# LEDDriver_v_6.net
KiCad netlist of a schematic drawn in EAGLE
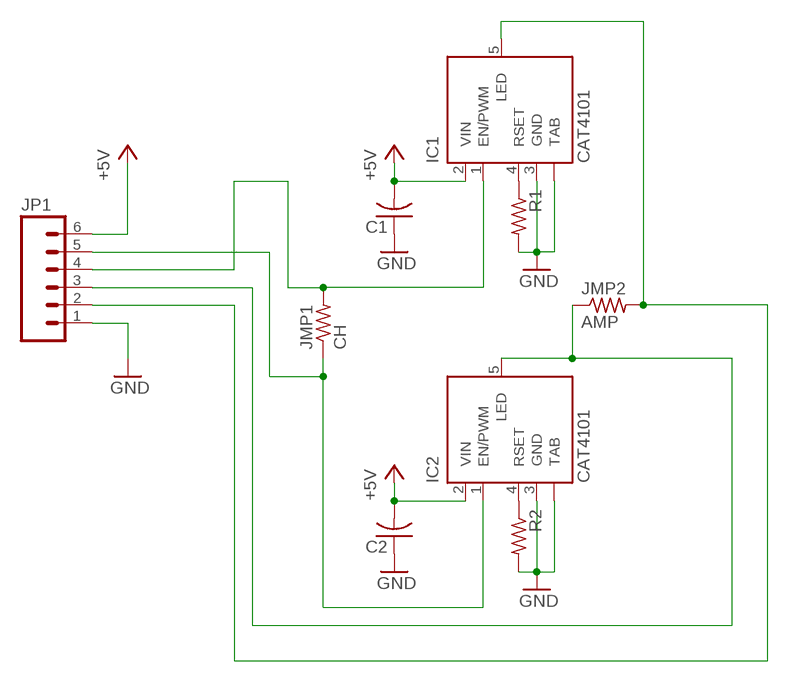
[diagram p0: schematic, sheet 1]

(export (version "E")
  (design (tool "Eeschema 10.0.6"))
  (components
    (comp (ref "C1")
      (value "C-USC1206")
      (footprint "eagle-import:C1206")
      (libsource (lib "eagle-import") (part "C-USC1206"))
    )
    (comp (ref "C2")
      (value "C-USC1206")
      (footprint "eagle-import:C1206")
      (libsource (lib "eagle-import") (part "C-USC1206"))
    )
    (comp (ref "IC1")
      (value "CAT4101")
      (footprint "eagle-import:TO263_5")
      (fields (field (name "MPN") "CAT4101TV-T75"))
      (libsource (lib "eagle-import") (part "CAT4101"))
    )
    (comp (ref "IC2")
      (value "CAT4101")
      (footprint "eagle-import:TO263_5")
      (fields (field (name "MPN") "CAT4101TV-T75"))
      (libsource (lib "eagle-import") (part "CAT4101"))
    )
    (comp (ref "JMP1")
      (value "CH")
      (footprint "eagle-import:R1206")
      (libsource (lib "eagle-import") (part "R-US_R1206"))
    )
    (comp (ref "JMP2")
      (value "AMP")
      (footprint "eagle-import:R1206")
      (libsource (lib "eagle-import") (part "R-US_R1206"))
    )
    (comp (ref "JP1")
      (value "M06LOCK_LONGPADS")
      (footprint "eagle-import:1X06_LOCK_LONGPADS")
      (libsource (lib "eagle-import") (part "M06LOCK_LONGPADS"))
    )
    (comp (ref "R1")
      (value "R-US_R1206")
      (footprint "eagle-import:R1206")
      (libsource (lib "eagle-import") (part "R-US_R1206"))
    )
    (comp (ref "R2")
      (value "R-US_R1206")
      (footprint "eagle-import:R1206")
      (libsource (lib "eagle-import") (part "R-US_R1206"))
    )
  )
  (nets
    (net (code "1") (name "+5V") (class "Default")
      (node (ref "C1") (pin "2") (pinfunction "2_2") (pintype "passive"))
      (node (ref "C2") (pin "2") (pinfunction "2_2") (pintype "passive"))
      (node (ref "IC1") (pin "2") (pinfunction "VIN_2") (pintype "input"))
      (node (ref "IC2") (pin "2") (pinfunction "VIN_2") (pintype "input"))
      (node (ref "JP1") (pin "6") (pinfunction "6_6") (pintype "passive"))
    )
    (net (code "2") (name "GND") (class "Default")
      (node (ref "C1") (pin "1") (pinfunction "1_1") (pintype "passive"))
      (node (ref "C2") (pin "1") (pinfunction "1_1") (pintype "passive"))
      (node (ref "IC1") (pin "3") (pinfunction "GND_3") (pintype "power_in"))
      (node (ref "IC1") (pin "TAB") (pinfunction "TAB_TAB") (pintype "passive"))
      (node (ref "IC2") (pin "3") (pinfunction "GND_3") (pintype "power_in"))
      (node (ref "IC2") (pin "TAB") (pinfunction "TAB_TAB") (pintype "passive"))
      (node (ref "JP1") (pin "1") (pinfunction "1_1") (pintype "passive"))
      (node (ref "R1") (pin "2") (pinfunction "2_2") (pintype "passive"))
      (node (ref "R2") (pin "2") (pinfunction "2_2") (pintype "passive"))
    )
    (net (code "3") (name "Net-(IC1-EN{slash}PWM)") (class "Default")
      (node (ref "IC1") (pin "1") (pinfunction "EN/PWM_1") (pintype "input"))
      (node (ref "JMP1") (pin "2") (pinfunction "2_2") (pintype "passive"))
      (node (ref "JP1") (pin "4") (pinfunction "4_4") (pintype "passive"))
    )
    (net (code "4") (name "Net-(IC1-LED)") (class "Default")
      (node (ref "IC1") (pin "5") (pinfunction "LED_5") (pintype "power_in"))
      (node (ref "JMP2") (pin "2") (pinfunction "2_2") (pintype "passive"))
      (node (ref "JP1") (pin "2") (pinfunction "2_2") (pintype "passive"))
    )
    (net (code "5") (name "Net-(IC1-RSET)") (class "Default")
      (node (ref "IC1") (pin "4") (pinfunction "RSET_4") (pintype "input"))
      (node (ref "R1") (pin "1") (pinfunction "1_1") (pintype "passive"))
    )
    (net (code "6") (name "Net-(IC2-EN{slash}PWM)") (class "Default")
      (node (ref "IC2") (pin "1") (pinfunction "EN/PWM_1") (pintype "input"))
      (node (ref "JMP1") (pin "1") (pinfunction "1_1") (pintype "passive"))
      (node (ref "JP1") (pin "5") (pinfunction "5_5") (pintype "passive"))
    )
    (net (code "7") (name "Net-(IC2-LED)") (class "Default")
      (node (ref "IC2") (pin "5") (pinfunction "LED_5") (pintype "power_in"))
      (node (ref "JMP2") (pin "1") (pinfunction "1_1") (pintype "passive"))
      (node (ref "JP1") (pin "3") (pinfunction "3_3") (pintype "passive"))
    )
    (net (code "8") (name "Net-(IC2-RSET)") (class "Default")
      (node (ref "IC2") (pin "4") (pinfunction "RSET_4") (pintype "input"))
      (node (ref "R2") (pin "1") (pinfunction "1_1") (pintype "passive"))
    )
  )
)
